# 5V_Supply.net
KiCad netlist of a schematic drawn in Altium Designer
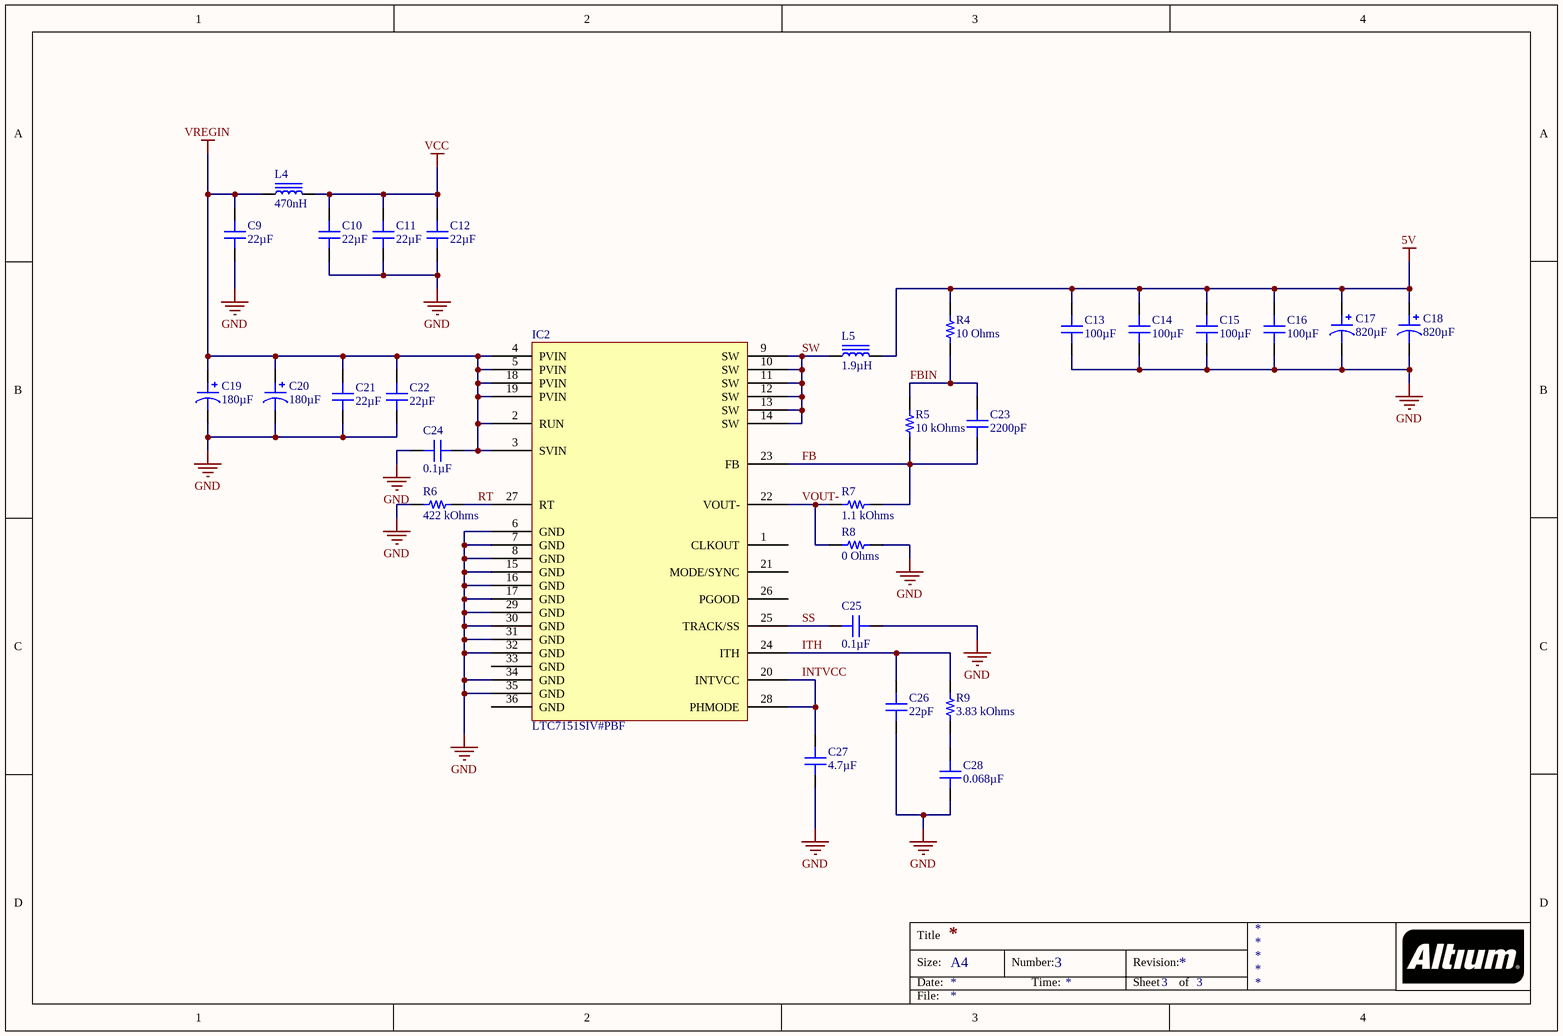
[diagram p0: 5V Supply.SchDoc]

(export (version "E")
  (design (tool "Eeschema 10.0.6"))
  (components
    (comp (ref "C9")
      (value "22µF")
      (footprint "CAP 1210_3225 - 2.8MM")
      (description "CAP CER 22UF 25V X5R 1210")
      (fields
        (field (name "PART NUMBER") "CL32A226KAJNNNE")
        (field (name "MANUFACTURER") "Samsung Electro-Mechanics")
      )
      (libsource (lib "Celestial Altium Library - altium_library") (part "Capacitor"))
    )
    (comp (ref "C10")
      (value "22µF")
      (footprint "CAP 1210_3225 - 2.8MM")
      (description "CAP CER 22UF 25V X5R 1210")
      (fields
        (field (name "PART NUMBER") "CL32A226KAJNNNE")
        (field (name "MANUFACTURER") "Samsung Electro-Mechanics")
      )
      (libsource (lib "Celestial Altium Library - altium_library") (part "Capacitor"))
    )
    (comp (ref "C11")
      (value "22µF")
      (footprint "CAP 2220_5650 3.0MM")
      (description "CAP CER 22UF 25V X7R 2220")
      (fields
        (field (name "MANUFACTURER") "TDK Corporation")
        (field (name "PART NUMBER") "C5750X7R1E226M250KA")
      )
      (libsource (lib "Celestial Altium Library - altium_library") (part "Capacitor"))
    )
    (comp (ref "C12")
      (value "22µF")
      (footprint "CAP 2220_5650 3.0MM")
      (description "CAP CER 22UF 25V X7R 2220")
      (fields
        (field (name "MANUFACTURER") "TDK Corporation")
        (field (name "PART NUMBER") "C5750X7R1E226M250KA")
      )
      (libsource (lib "Celestial Altium Library - altium_library") (part "Capacitor"))
    )
    (comp (ref "C13")
      (value "100µF")
      (footprint "CAP 2220_5650 3.3MM")
      (description "CAP CER 100UF 10V X5R 2220")
      (fields
        (field (name "MANUFACTURER") "TDK Corporation")
        (field (name "PART NUMBER") "C5750X5R1A107M280KC")
      )
      (libsource (lib "Celestial Altium Library - altium_library") (part "Capacitor"))
    )
    (comp (ref "C14")
      (value "100µF")
      (footprint "CAP 2220_5650 3.3MM")
      (description "CAP CER 100UF 10V X5R 2220")
      (fields
        (field (name "MANUFACTURER") "TDK Corporation")
        (field (name "PART NUMBER") "C5750X5R1A107M280KC")
      )
      (libsource (lib "Celestial Altium Library - altium_library") (part "Capacitor"))
    )
    (comp (ref "C15")
      (value "100µF")
      (footprint "CAP 2220_5650 3.3MM")
      (description "CAP CER 100UF 10V X5R 2220")
      (fields
        (field (name "MANUFACTURER") "TDK Corporation")
        (field (name "PART NUMBER") "C5750X5R1A107M280KC")
      )
      (libsource (lib "Celestial Altium Library - altium_library") (part "Capacitor"))
    )
    (comp (ref "C16")
      (value "100µF")
      (footprint "CAP 2220_5650 3.3MM")
      (description "CAP CER 100UF 10V X5R 2220")
      (fields
        (field (name "MANUFACTURER") "TDK Corporation")
        (field (name "PART NUMBER") "C5750X5R1A107M280KC")
      )
      (libsource (lib "Celestial Altium Library - altium_library") (part "Capacitor"))
    )
    (comp (ref "C17")
      (value "820µF")
      (footprint "CAP ALSMD POLY 8.3MM H10.0MM")
      (description "CAP ALUM POLY 820UF 20% 6.3V SMD")
      (fields (field (name "PART NUMBER") "A765KN827M0JLAE010") (field (name "MANUFACTURER") "KEMET"))
      (libsource (lib "Celestial Altium Library - altium_library") (part "Polarised Capacitor"))
    )
    (comp (ref "C18")
      (value "820µF")
      (footprint "CAP ALSMD POLY 8.3MM H10.0MM")
      (description "CAP ALUM POLY 820UF 20% 6.3V SMD")
      (fields (field (name "PART NUMBER") "A765KN827M0JLAE010") (field (name "MANUFACTURER") "KEMET"))
      (libsource (lib "Celestial Altium Library - altium_library") (part "Polarised Capacitor"))
    )
    (comp (ref "C19")
      (value "180µF")
      (footprint "CAP ALSMD POLY 8.3MM H7.0MM")
      (description "CAP ALUM POLY 180UF 20% 20V SMD")
      (fields
        (field (name "PART NUMBER") "APXG200ARA181MH70G")
        (field (name "MANUFACTURER") "United Chemi-Con")
      )
      (libsource (lib "Celestial Altium Library - altium_library") (part "Polarised Capacitor"))
    )
    (comp (ref "C20")
      (value "180µF")
      (footprint "CAP ALSMD POLY 8.3MM H7.0MM")
      (description "CAP ALUM POLY 180UF 20% 20V SMD")
      (fields
        (field (name "PART NUMBER") "APXG200ARA181MH70G")
        (field (name "MANUFACTURER") "United Chemi-Con")
      )
      (libsource (lib "Celestial Altium Library - altium_library") (part "Polarised Capacitor"))
    )
    (comp (ref "C21")
      (value "22µF")
      (footprint "CAP 2220_5650 3.0MM")
      (description "CAP CER 22UF 25V X7R 2220")
      (fields
        (field (name "MANUFACTURER") "TDK Corporation")
        (field (name "PART NUMBER") "C5750X7R1E226M250KA")
      )
      (libsource (lib "Celestial Altium Library - altium_library") (part "Capacitor"))
    )
    (comp (ref "C22")
      (value "22µF")
      (footprint "CAP 2220_5650 3.0MM")
      (description "CAP CER 22UF 25V X7R 2220")
      (fields
        (field (name "MANUFACTURER") "TDK Corporation")
        (field (name "PART NUMBER") "C5750X7R1E226M250KA")
      )
      (libsource (lib "Celestial Altium Library - altium_library") (part "Capacitor"))
    )
    (comp (ref "C23")
      (value "2200pF")
      (footprint "CAP 0603_1608")
      (description "CAP CER 2200PF 100V X7R 0603")
      (fields (field (name "PART NUMBER") "CC0603KRX7R0BB222") (field (name "MANUFACTURER") "Yageo"))
      (libsource (lib "Celestial Altium Library - altium_library") (part "Capacitor"))
    )
    (comp (ref "C24")
      (value "0.1µF")
      (footprint "CAP 0603_1608")
      (description "CAP CER 0.1UF 50V X7R 0603")
      (fields (field (name "PART NUMBER") "06035C104JAT4A") (field (name "MANUFACTURER") "AVX Corporation"))
      (libsource (lib "Celestial Altium Library - altium_library") (part "Capacitor"))
    )
    (comp (ref "C25")
      (value "0.1µF")
      (footprint "CAP 0603_1608")
      (description "CAP CER 0.1UF 50V X7R 0603")
      (fields (field (name "PART NUMBER") "06035C104JAT4A") (field (name "MANUFACTURER") "AVX Corporation"))
      (libsource (lib "Celestial Altium Library - altium_library") (part "Capacitor"))
    )
    (comp (ref "C26")
      (value "22pF")
      (footprint "CAP 0603_1608")
      (description "CAP CER 22PF 25V NPO 0603")
      (fields (field (name "PART NUMBER") "CC0603JRNPO8BN220") (field (name "MANUFACTURER") "Yageo"))
      (libsource (lib "Celestial Altium Library - altium_library") (part "Capacitor"))
    )
    (comp (ref "C27")
      (value "4.7µF")
      (footprint "CAP 0603_1608")
      (description "CAP CER 4.7UF 10V X5R 0603")
      (fields
        (field (name "PART NUMBER") "CL10A475MP8NNNC")
        (field (name "MANUFACTURER") "Samsung Electro-Mechanics")
      )
      (libsource (lib "Celestial Altium Library - altium_library") (part "Capacitor"))
    )
    (comp (ref "C28")
      (value "0.068µF")
      (footprint "CAP 0603_1608")
      (description "CAP CER 0.068UF 50V X7R 0603")
      (fields
        (field (name "PART NUMBER") "0603B683K500CT")
        (field (name "MANUFACTURER") "Walsin Technology Corporation")
      )
      (libsource (lib "Celestial Altium Library - altium_library") (part "Capacitor"))
    )
    (comp (ref "IC2")
      (value "LTC7151SIV#PBF")
      (footprint "ANALOG LQFN-28 5x4MM")
      (description "IC REG BUCK ADJ 15A 28LQFN")
      (fields (field (name "MANUFACTURER") "Linear Technology/Analog Devices"))
      (libsource (lib "Celestial Altium Library - altium_library") (part "ANALOG LTC7151S"))
    )
    (comp (ref "L4")
      (value "470nH")
      (footprint "WURTH WE-HCM H9.0MM")
      (description "FIXED IND 470NH 47.5A 0.165 MOHM")
      (fields (field (name "PART NUMBER") "744309047") (field (name "MANUFACTURER") "Würth Elektronik"))
      (libsource (lib "Celestial Altium Library - altium_library") (part "Inductor"))
    )
    (comp (ref "L5")
      (value "1.9µH")
      (footprint "WURTH WE-HCL 1830 H9.0MM")
      (description "FIXED IND 1.9UH 32.5A 1.2 MOHM")
      (fields (field (name "PART NUMBER") "7443556190") (field (name "MANUFACTURER") "Würth Elektronik"))
      (libsource (lib "Celestial Altium Library - altium_library") (part "Inductor"))
    )
    (comp (ref "R4")
      (value "10 Ohms")
      (footprint "RES 0603_1608")
      (description "RES SMD 10 OHM 1% 1/10W 0603")
      (fields
        (field (name "PART NUMBER") "ERJ-3EKF10R0V")
        (field (name "MANUFACTURER") "Panasonic Electronic Components")
      )
      (libsource (lib "Celestial Altium Library - altium_library") (part "Resistor"))
    )
    (comp (ref "R5")
      (value "10 kOhms")
      (footprint "RES 0603_1608")
      (description "RES SMD 10K OHM 1% 1/10W 0603")
      (fields
        (field (name "PART NUMBER") "ERJ-3EKF1002V")
        (field (name "MANUFACTURER") "Panasonic Electronic Components")
      )
      (libsource (lib "Celestial Altium Library - altium_library") (part "Resistor"))
    )
    (comp (ref "R6")
      (value "422 kOhms")
      (footprint "RES 0603_1608")
      (description "RES SMD 422K OHM 1% 1/10W 0603")
      (fields
        (field (name "PART NUMBER") "ERJ-3EKF4223V")
        (field (name "MANUFACTURER") "Panasonic Electronic Components")
      )
      (libsource (lib "Celestial Altium Library - altium_library") (part "Resistor"))
    )
    (comp (ref "R7")
      (value "1.1 kOhms")
      (footprint "RES 0603_1608")
      (description "RES SMD 1.1K OHM 1% 1/10W 0603")
      (fields
        (field (name "PART NUMBER") "ERJ-3EKF1101V")
        (field (name "MANUFACTURER") "Panasonic Electronic Components")
      )
      (libsource (lib "Celestial Altium Library - altium_library") (part "Resistor"))
    )
    (comp (ref "R8")
      (value "0 Ohms")
      (footprint "RES 0603_1608")
      (description "RES SMD 0 OHM JUMPER 1/10W 0603")
      (fields
        (field (name "PART NUMBER") "ERJ-3GEY0R00V")
        (field (name "MANUFACTURER") "Panasonic Electronic Components")
      )
      (libsource (lib "Celestial Altium Library - altium_library") (part "Resistor"))
    )
    (comp (ref "R9")
      (value "3.83 kOhms")
      (footprint "RES 0603_1608")
      (description "RES SMD 3.83K OHM 1% 1/10W 0603")
      (fields
        (field (name "PART NUMBER") "ERJ-3EKF3831V")
        (field (name "MANUFACTURER") "Panasonic Electronic Components")
      )
      (libsource (lib "Celestial Altium Library - altium_library") (part "Resistor"))
    )
  )
  (nets
    (net (code "1") (name "/FB") (class "Default")
      (node (ref "C23") (pin "1") (pinfunction "1_1") (pintype "passive"))
      (node (ref "IC2") (pin "23") (pinfunction "FB_23") (pintype "passive"))
      (node (ref "R5") (pin "1") (pinfunction "1_1") (pintype "passive"))
      (node (ref "R7") (pin "2") (pinfunction "2_2") (pintype "passive"))
    )
    (net (code "2") (name "/FBIN") (class "Default")
      (node (ref "C23") (pin "2") (pinfunction "2_2") (pintype "passive"))
      (node (ref "R4") (pin "1") (pinfunction "1_1") (pintype "passive"))
      (node (ref "R5") (pin "2") (pinfunction "2_2") (pintype "passive"))
    )
    (net (code "3") (name "/INTVCC") (class "Default")
      (node (ref "C27") (pin "2") (pinfunction "2_2") (pintype "passive"))
      (node (ref "IC2") (pin "20") (pinfunction "INTVCC_20") (pintype "passive"))
      (node (ref "IC2") (pin "28") (pinfunction "PHMODE_28") (pintype "passive"))
    )
    (net (code "4") (name "/ITH") (class "Default")
      (node (ref "C26") (pin "2") (pinfunction "2_2") (pintype "passive"))
      (node (ref "IC2") (pin "24") (pinfunction "ITH_24") (pintype "passive"))
      (node (ref "R9") (pin "2") (pinfunction "2_2") (pintype "passive"))
    )
    (net (code "5") (name "/RT") (class "Default")
      (node (ref "IC2") (pin "27") (pinfunction "RT_27") (pintype "passive"))
      (node (ref "R6") (pin "2") (pinfunction "2_2") (pintype "passive"))
    )
    (net (code "6") (name "/SS") (class "Default")
      (node (ref "C25") (pin "2") (pinfunction "2_2") (pintype "passive"))
      (node (ref "IC2") (pin "25") (pinfunction "TRACK/SS_25") (pintype "passive"))
    )
    (net (code "7") (name "/SW") (class "Default")
      (node (ref "IC2") (pin "10") (pinfunction "SW_10") (pintype "passive"))
      (node (ref "IC2") (pin "11") (pinfunction "SW_11") (pintype "passive"))
      (node (ref "IC2") (pin "12") (pinfunction "SW_12") (pintype "passive"))
      (node (ref "IC2") (pin "13") (pinfunction "SW_13") (pintype "passive"))
      (node (ref "IC2") (pin "14") (pinfunction "SW_14") (pintype "passive"))
      (node (ref "IC2") (pin "9") (pinfunction "SW_9") (pintype "passive"))
      (node (ref "L5") (pin "1") (pinfunction "1_1") (pintype "passive"))
    )
    (net (code "8") (name "/VOUT-") (class "Default")
      (node (ref "IC2") (pin "22") (pinfunction "VOUT-_22") (pintype "passive"))
      (node (ref "R7") (pin "1") (pinfunction "1_1") (pintype "passive"))
      (node (ref "R8") (pin "1") (pinfunction "1_1") (pintype "passive"))
    )
    (net (code "9") (name "5V") (class "Default")
      (node (ref "C13") (pin "2") (pinfunction "2_2") (pintype "passive"))
      (node (ref "C14") (pin "2") (pinfunction "2_2") (pintype "passive"))
      (node (ref "C15") (pin "2") (pinfunction "2_2") (pintype "passive"))
      (node (ref "C16") (pin "2") (pinfunction "2_2") (pintype "passive"))
      (node (ref "C17") (pin "1") (pinfunction "1_1") (pintype "passive"))
      (node (ref "C18") (pin "1") (pinfunction "1_1") (pintype "passive"))
      (node (ref "L5") (pin "2") (pinfunction "2_2") (pintype "passive"))
      (node (ref "R4") (pin "2") (pinfunction "2_2") (pintype "passive"))
    )
    (net (code "10") (name "GND") (class "Default")
      (node (ref "C10") (pin "1") (pinfunction "1_1") (pintype "passive"))
      (node (ref "C11") (pin "1") (pinfunction "1_1") (pintype "passive"))
      (node (ref "C12") (pin "1") (pinfunction "1_1") (pintype "passive"))
      (node (ref "C13") (pin "1") (pinfunction "1_1") (pintype "passive"))
      (node (ref "C14") (pin "1") (pinfunction "1_1") (pintype "passive"))
      (node (ref "C15") (pin "1") (pinfunction "1_1") (pintype "passive"))
      (node (ref "C16") (pin "1") (pinfunction "1_1") (pintype "passive"))
      (node (ref "C17") (pin "2") (pinfunction "2_2") (pintype "passive"))
      (node (ref "C18") (pin "2") (pinfunction "2_2") (pintype "passive"))
      (node (ref "C19") (pin "2") (pinfunction "2_2") (pintype "passive"))
      (node (ref "C20") (pin "2") (pinfunction "2_2") (pintype "passive"))
      (node (ref "C21") (pin "1") (pinfunction "1_1") (pintype "passive"))
      (node (ref "C22") (pin "1") (pinfunction "1_1") (pintype "passive"))
      (node (ref "C24") (pin "1") (pinfunction "1_1") (pintype "passive"))
      (node (ref "C25") (pin "1") (pinfunction "1_1") (pintype "passive"))
      (node (ref "C26") (pin "1") (pinfunction "1_1") (pintype "passive"))
      (node (ref "C27") (pin "1") (pinfunction "1_1") (pintype "passive"))
      (node (ref "C28") (pin "1") (pinfunction "1_1") (pintype "passive"))
      (node (ref "C9") (pin "1") (pinfunction "1_1") (pintype "passive"))
      (node (ref "IC2") (pin "15") (pinfunction "GND_15") (pintype "passive"))
      (node (ref "IC2") (pin "16") (pinfunction "GND_16") (pintype "passive"))
      (node (ref "IC2") (pin "17") (pinfunction "GND_17") (pintype "passive"))
      (node (ref "IC2") (pin "29") (pinfunction "GND_29") (pintype "passive"))
      (node (ref "IC2") (pin "30") (pinfunction "GND_30") (pintype "passive"))
      (node (ref "IC2") (pin "31") (pinfunction "GND_31") (pintype "passive"))
      (node (ref "IC2") (pin "32") (pinfunction "GND_32") (pintype "passive"))
      (node (ref "IC2") (pin "34") (pinfunction "GND_34") (pintype "passive"))
      (node (ref "IC2") (pin "35") (pinfunction "GND_35") (pintype "passive"))
      (node (ref "IC2") (pin "6") (pinfunction "GND_6") (pintype "passive"))
      (node (ref "IC2") (pin "7") (pinfunction "GND_7") (pintype "passive"))
      (node (ref "IC2") (pin "8") (pinfunction "GND_8") (pintype "passive"))
      (node (ref "R6") (pin "1") (pinfunction "1_1") (pintype "passive"))
      (node (ref "R8") (pin "2") (pinfunction "2_2") (pintype "passive"))
    )
    (net (code "11") (name "Net-(C28-Pad2)") (class "Default")
      (node (ref "C28") (pin "2") (pinfunction "2_2") (pintype "passive"))
      (node (ref "R9") (pin "1") (pinfunction "1_1") (pintype "passive"))
    )
    (net (code "12") (name "VCC") (class "Default")
      (node (ref "C10") (pin "2") (pinfunction "2_2") (pintype "passive"))
      (node (ref "C11") (pin "2") (pinfunction "2_2") (pintype "passive"))
      (node (ref "C12") (pin "2") (pinfunction "2_2") (pintype "passive"))
      (node (ref "L4") (pin "2") (pinfunction "2_2") (pintype "passive"))
    )
    (net (code "13") (name "VREGIN") (class "Default")
      (node (ref "C19") (pin "1") (pinfunction "1_1") (pintype "passive"))
      (node (ref "C20") (pin "1") (pinfunction "1_1") (pintype "passive"))
      (node (ref "C21") (pin "2") (pinfunction "2_2") (pintype "passive"))
      (node (ref "C22") (pin "2") (pinfunction "2_2") (pintype "passive"))
      (node (ref "C24") (pin "2") (pinfunction "2_2") (pintype "passive"))
      (node (ref "C9") (pin "2") (pinfunction "2_2") (pintype "passive"))
      (node (ref "IC2") (pin "18") (pinfunction "PVIN_18") (pintype "passive"))
      (node (ref "IC2") (pin "19") (pinfunction "PVIN_19") (pintype "passive"))
      (node (ref "IC2") (pin "2") (pinfunction "RUN_2") (pintype "passive"))
      (node (ref "IC2") (pin "3") (pinfunction "SVIN_3") (pintype "passive"))
      (node (ref "IC2") (pin "4") (pinfunction "PVIN_4") (pintype "passive"))
      (node (ref "IC2") (pin "5") (pinfunction "PVIN_5") (pintype "passive"))
      (node (ref "L4") (pin "1") (pinfunction "1_1") (pintype "passive"))
    )
    (net (code "14") (name "unconnected-(IC2-CLKOUT-Pad1)") (class "Default")
      (node (ref "IC2") (pin "1") (pinfunction "CLKOUT_1") (pintype "passive"))
    )
    (net (code "15") (name "unconnected-(IC2-GND-Pad33)") (class "Default")
      (node (ref "IC2") (pin "33") (pinfunction "GND_33") (pintype "passive"))
    )
    (net (code "16") (name "unconnected-(IC2-GND-Pad36)") (class "Default")
      (node (ref "IC2") (pin "36") (pinfunction "GND_36") (pintype "passive"))
    )
    (net (code "17") (name "unconnected-(IC2-MODE{slash}SYNC-Pad21)") (class "Default")
      (node (ref "IC2") (pin "21") (pinfunction "MODE/SYNC_21") (pintype "passive"))
    )
    (net (code "18") (name "unconnected-(IC2-PGOOD-Pad26)") (class "Default")
      (node (ref "IC2") (pin "26") (pinfunction "PGOOD_26") (pintype "passive"))
    )
  )
)
